# SPE_router_spe.net
KiCad netlist of a schematic drawn in Altium Designer
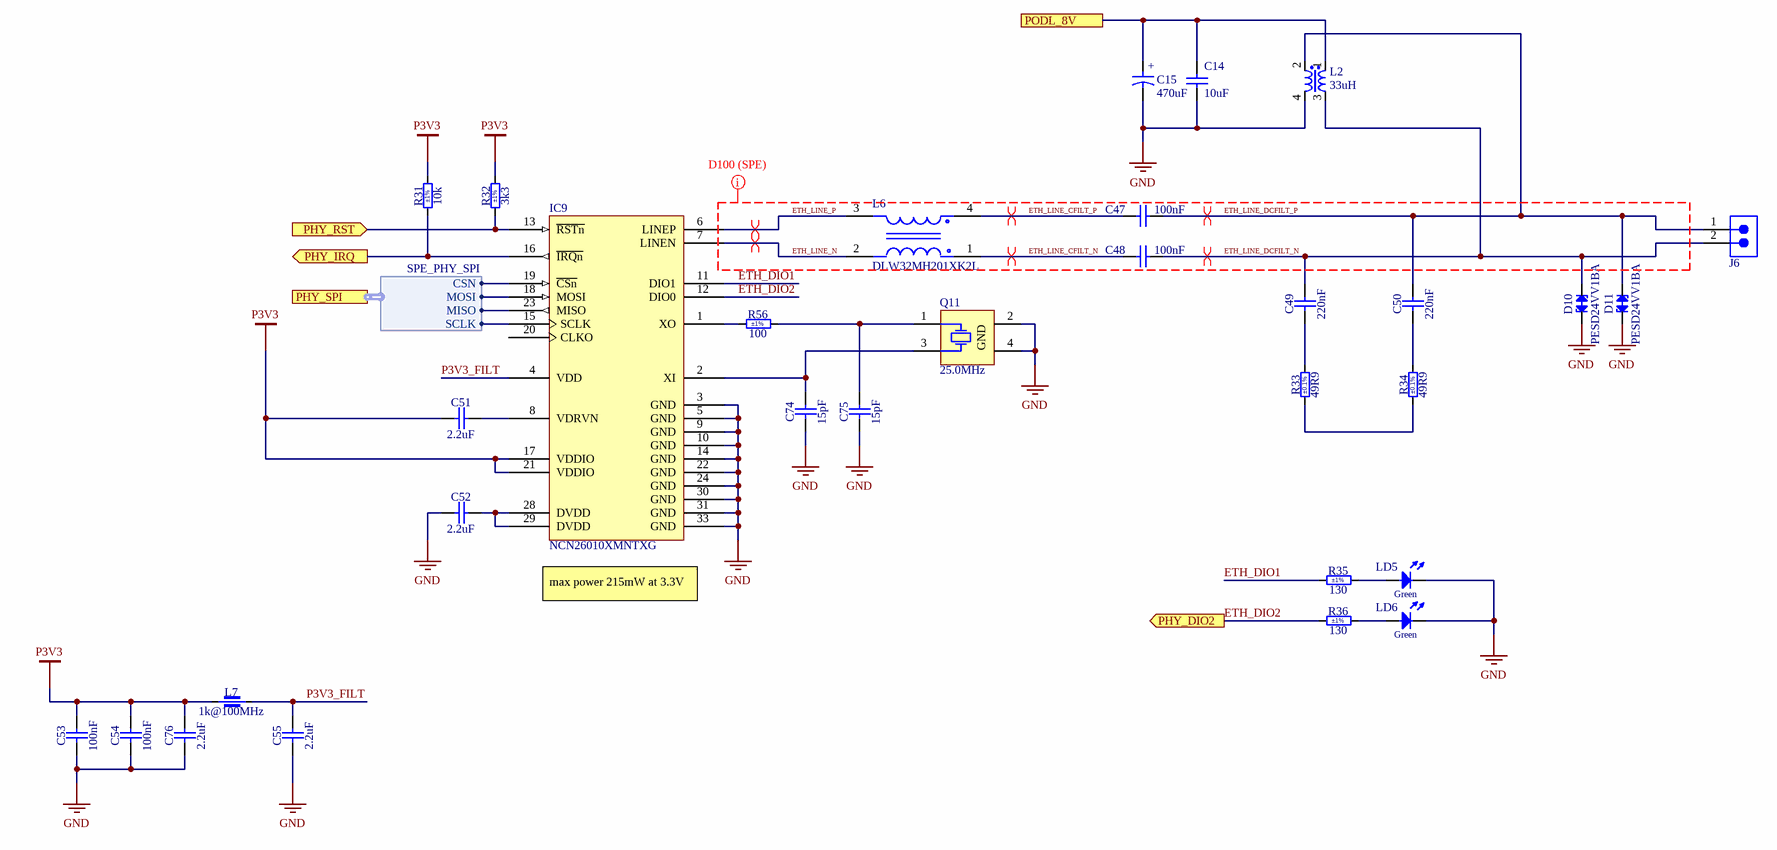
[diagram p0: SPE_router_spe.SchDoc]

(export (version "E")
  (design (tool "Eeschema 10.0.6"))
  (components
    (comp (ref "C14")
      (value "10uF")
      (footprint "CAPC3216X180N")
      (description "Non-polarised capacitor")
      (fields
        (field (name "PART NUMBER") "CC1206_10UF_25V_10%_X7R")
        (field (name "VOLTAGE") "25V")
        (field (name "AUTHOR") "CERN DEM JLC")
      )
      (libsource (lib "Capacitors") (part "Capacitor - non polarized"))
    )
    (comp (ref "C15")
      (value "470uF")
      (footprint "CAPAE830X1020N")
      (description "Polarised capacitor")
      (fields
        (field (name "PART NUMBER") "CAE830-1020_470UF_16V_20%")
        (field (name "VOLTAGE") "16V")
        (field (name "AUTHOR") "CERN DEM JLC")
      )
      (libsource (lib "Capacitors") (part "Capacitor - polarized"))
    )
    (comp (ref "C47")
      (value "100nF")
      (footprint "CAPC1005X55N")
      (description "Non-polarised capacitor")
      (fields (field (name "PART NUMBER") "CC0402_100NF_50V_10%_X7R"))
      (libsource (lib "Capacitors") (part "Capacitor - non polarized"))
    )
    (comp (ref "C48")
      (value "100nF")
      (footprint "CAPC1005X55N")
      (description "Non-polarised capacitor")
      (fields (field (name "PART NUMBER") "CC0402_100NF_50V_10%_X7R"))
      (libsource (lib "Capacitors") (part "Capacitor - non polarized"))
    )
    (comp (ref "C49")
      (value "220nF")
      (footprint "CAPC2012X135N")
      (description "Non-polarised capacitor")
      (fields
        (field (name "PART NUMBER") "CC0805_220NF_100V_10%_X7R")
        (field (name "VOLTAGE") "100V")
        (field (name "AUTHOR") "CERN DEM JLC")
      )
      (libsource (lib "Capacitors") (part "Capacitor - non polarized"))
    )
    (comp (ref "C50")
      (value "220nF")
      (footprint "CAPC2012X135N")
      (description "Non-polarised capacitor")
      (fields
        (field (name "PART NUMBER") "CC0805_220NF_100V_10%_X7R")
        (field (name "VOLTAGE") "100V")
        (field (name "AUTHOR") "CERN DEM JLC")
      )
      (libsource (lib "Capacitors") (part "Capacitor - non polarized"))
    )
    (comp (ref "C51")
      (value "2.2uF")
      (footprint "CAPC1005X55N")
      (description "Non-polarised capacitor")
      (fields (field (name "PART NUMBER") "CC0402_2.2UF_6.3V_10%_X5R"))
      (libsource (lib "Capacitors") (part "Capacitor - non polarized"))
    )
    (comp (ref "C52")
      (value "2.2uF")
      (footprint "CAPC1005X55N")
      (description "Non-polarised capacitor")
      (fields (field (name "PART NUMBER") "CC0402_2.2UF_6.3V_10%_X5R"))
      (libsource (lib "Capacitors") (part "Capacitor - non polarized"))
    )
    (comp (ref "C53")
      (value "100nF")
      (footprint "CAPC1005X55N")
      (description "Non-polarised capacitor")
      (fields
        (field (name "PART NUMBER") "CC0402_100NF_16V_10%_X7R")
        (field (name "VOLTAGE") "16V")
        (field (name "AUTHOR") "CERN DEM JLC")
      )
      (libsource (lib "Capacitors") (part "Capacitor - non polarized"))
    )
    (comp (ref "C54")
      (value "100nF")
      (footprint "CAPC1005X55N")
      (description "Non-polarised capacitor")
      (fields
        (field (name "PART NUMBER") "CC0402_100NF_16V_10%_X7R")
        (field (name "VOLTAGE") "16V")
        (field (name "AUTHOR") "CERN DEM JLC")
      )
      (libsource (lib "Capacitors") (part "Capacitor - non polarized"))
    )
    (comp (ref "C55")
      (value "2.2uF")
      (footprint "CAPC1005X55N")
      (description "Non-polarised capacitor")
      (fields (field (name "PART NUMBER") "CC0402_2.2UF_6.3V_10%_X5R"))
      (libsource (lib "Capacitors") (part "Capacitor - non polarized"))
    )
    (comp (ref "C74")
      (value "15pF")
      (footprint "CAPC1005X55N")
      (description "Non-polarised capacitor")
      (fields
        (field (name "PART NUMBER") "CC0402_15PF_50V_5%_C0G")
        (field (name "VOLTAGE") "50V")
        (field (name "AUTHOR") "CERN DEM JLC")
      )
      (libsource (lib "Capacitors") (part "Capacitor - non polarized"))
    )
    (comp (ref "C75")
      (value "15pF")
      (footprint "CAPC1005X55N")
      (description "Non-polarised capacitor")
      (fields
        (field (name "PART NUMBER") "CC0402_15PF_50V_5%_C0G")
        (field (name "VOLTAGE") "50V")
        (field (name "AUTHOR") "CERN DEM JLC")
      )
      (libsource (lib "Capacitors") (part "Capacitor - non polarized"))
    )
    (comp (ref "C76")
      (value "2.2uF")
      (footprint "CAPC1005X55N")
      (description "Non-polarised capacitor")
      (fields (field (name "PART NUMBER") "CC0402_2.2UF_6.3V_10%_X5R"))
      (libsource (lib "Capacitors") (part "Capacitor - non polarized"))
    )
    (comp (ref "D10")
      (value "PESD24VV1BA")
      (footprint "SOD2512X110N")
      (description "Bi-Directional ESD Protection Diode")
      (fields
        (field (name "VOLTAGE") "24V")
        (field (name "POWER") "200W")
        (field (name "AUTHOR") "CERN DEM JLC")
      )
      (libsource (lib "ICs And Semiconductors") (part "Diode ESD Bi-Directional"))
    )
    (comp (ref "D11")
      (value "PESD24VV1BA")
      (footprint "SOD2512X110N")
      (description "Bi-Directional ESD Protection Diode")
      (fields
        (field (name "VOLTAGE") "24V")
        (field (name "POWER") "200W")
        (field (name "AUTHOR") "CERN DEM JLC")
      )
      (libsource (lib "ICs And Semiconductors") (part "Diode ESD Bi-Directional"))
    )
    (comp (ref "IC9")
      (value "NCN26010XMNTXG")
      (footprint "QFN40P400X400X100_HS-33N")
      (description "Ethernet Controller, 10 Mb/s, Single-Pair, MAC + PHY, 802.3cg, 10BASE−T1S Compliant")
      (fields (field (name "MANUFACTURER") "ON Semiconductor"))
      (libsource (lib "DiPho_lib") (part "NCN26010XMNTXG"))
    )
    (comp (ref "J6")
      (value "691382040002")
      (footprint "691382040002")
      (description "WR-TBL Series 382 Horizontal PCB Header with Flanges, THT, pitch 2.5mm, 2p")
      (fields (field (name "MANUFACTURER") "Wurth Elektronik"))
      (libsource (lib "SPE_router_lib") (part "691382040002"))
    )
    (comp (ref "L2")
      (value "33uH")
      (footprint "MSD1278H-333MED")
      (description "coupled inductor, ferrite core, SMT, RoHS")
      (fields
        (field (name "MANUFACTURER") "Coilcraft")
        (field (name "MANUFACTURER PART NUMBER") "MSD1278H-333MED")
      )
      (libsource (lib "SPE_router_lib") (part "MSD1278H-333MED"))
    )
    (comp (ref "L6")
      (value "DLW32MH201XK2L")
      (footprint "FP-DLW32MH201XK2L-MFG")
      (description "200UH-20%/+50% (AT 0.1MHZ)70MA R")
      (fields
        (field (name "OCTOPART") "https://octopart.com/dlw32mh201xk2l-murata-91401020")
        (field (name "MANUFACTURER") "Murata")
      )
      (libsource (lib "Altium Content Vault") (part "fd31f9bded309692d3ecdb47de416e9"))
    )
    (comp (ref "L7")
      (value "1k@100MHz")
      (footprint "INDC1608X100N")
      (fields
        (field (name "PART NUMBER") "IND0603_WURTH_74279266")
        (field (name "POWER") "200mA")
        (field (name "TOLERANCE") "±25%")
        (field (name "AUTHOR") "CERN DEM JLC")
      )
      (libsource (lib "Inductors & Transformers") (part "Ferrite Bead"))
    )
    (comp (ref "LD5")
      (value "Green")
      (footprint "LED_AVAGO_HSME-C110")
      (description "LED Green 1C 2A")
      (fields
        (field (name "PART NUMBER") "LED_AVAGO_HSME-C110")
        (field (name "MANUFACTURER") "AVAGO TECHNOLOGIES")
        (field (name "AUTHOR") "CERN DEM JMW")
      )
      (libsource (lib "ICs And Semiconductors") (part "LED Green 1C 2A"))
    )
    (comp (ref "LD6")
      (value "Green")
      (footprint "LED_AVAGO_HSME-C110")
      (description "LED Green 1C 2A")
      (fields
        (field (name "PART NUMBER") "LED_AVAGO_HSME-C110")
        (field (name "MANUFACTURER") "AVAGO TECHNOLOGIES")
        (field (name "AUTHOR") "CERN DEM JMW")
      )
      (libsource (lib "ICs And Semiconductors") (part "LED Green 1C 2A"))
    )
    (comp (ref "Q11")
      (value "25.0MHz")
      (footprint "XTAL_KYOCERA_CX3225SB")
      (description "Crystal 25 Mhz 12PF SMD")
      (fields
        (field (name "MANUFACTURER") "ECS International")
        (field (name "MANUFACTURER PART NUMBER") "ECS-250-12-33B-CWY-TR3")
      )
      (libsource (lib "SPE_router_lib") (part "ECS-250-12-33B-CWY-TR3"))
    )
    (comp (ref "R31")
      (value "10k")
      (footprint "RESC1005X40N")
      (description "Resistor - 1%")
      (fields
        (field (name "TOLERANCE") "±1%")
        (field (name "PART NUMBER") "R0402_10K_1%_0.0625W_100PPM")
        (field (name "POWER") "0.0625W")
        (field (name "AUTHOR") "CERN DEM JLC")
      )
      (libsource (lib "Resistors") (part "Resistor - 1%"))
    )
    (comp (ref "R32")
      (value "3k3")
      (footprint "RESC1005X40N")
      (description "Resistor - 1%")
      (fields
        (field (name "TOLERANCE") "±1%")
        (field (name "PART NUMBER") "R0402_3K3_1%_0.0625W_100PPM")
        (field (name "POWER") "0.0625W")
        (field (name "AUTHOR") "CERN DEM JLC")
      )
      (libsource (lib "Resistors") (part "Resistor - 1%"))
    )
    (comp (ref "R33")
      (value "49R9")
      (footprint "RESC1608X55N")
      (description "Resistor - 0.1%")
      (fields
        (field (name "TOLERANCE") "±0.1%")
        (field (name "PART NUMBER") "R0603_49R9_0.1%_0.063W_10PPM")
        (field (name "POWER") "0.063W")
        (field (name "AUTHOR") "CERN DEM JLC")
      )
      (libsource (lib "Resistors") (part "Resistor - 0.1%"))
    )
    (comp (ref "R34")
      (value "49R9")
      (footprint "RESC1608X55N")
      (description "Resistor - 0.1%")
      (fields
        (field (name "TOLERANCE") "±0.1%")
        (field (name "PART NUMBER") "R0603_49R9_0.1%_0.063W_10PPM")
        (field (name "POWER") "0.063W")
        (field (name "AUTHOR") "CERN DEM JLC")
      )
      (libsource (lib "Resistors") (part "Resistor - 0.1%"))
    )
    (comp (ref "R35")
      (value "130")
      (footprint "RESC1005X40N")
      (description "Resistor - 1%")
      (fields
        (field (name "TOLERANCE") "±1%")
        (field (name "PART NUMBER") "R0402_130R_1%_0.0625W_100PPM")
        (field (name "POWER") "0.0625W")
        (field (name "AUTHOR") "CERN DEM JLC")
      )
      (libsource (lib "Resistors") (part "Resistor - 1%"))
    )
    (comp (ref "R36")
      (value "130")
      (footprint "RESC1005X40N")
      (description "Resistor - 1%")
      (fields
        (field (name "TOLERANCE") "±1%")
        (field (name "PART NUMBER") "R0402_130R_1%_0.0625W_100PPM")
        (field (name "POWER") "0.0625W")
        (field (name "AUTHOR") "CERN DEM JLC")
      )
      (libsource (lib "Resistors") (part "Resistor - 1%"))
    )
    (comp (ref "R56")
      (value "100")
      (footprint "RESC1005X40N")
      (description "Resistor - 1%")
      (fields
        (field (name "PART NUMBER") "R0402_100R_1%_0.0625W_100PPM")
        (field (name "MANUFACTURER") "GENERIC")
        (field (name "TOLERANCE") "±1%")
        (field (name "AUTHOR") "CERN DEM JLC")
      )
      (libsource (lib "Resistors") (part "Resistor - 1%"))
    )
  )
  (nets
    (net (code "2") (name "/CSN") (class "Default")
      (node (ref "IC9") (pin "19") (pinfunction "~{CSn}_19") (pintype "input"))
    )
    (net (code "3") (name "/ETH_DIO1") (class "Default")
      (node (ref "IC9") (pin "11") (pinfunction "DIO1_11") (pintype "passive"))
      (node (ref "R35") (pin "1") (pinfunction "1_1") (pintype "passive"))
    )
    (net (code "4") (name "/ETH_DIO2") (class "Default")
      (node (ref "IC9") (pin "12") (pinfunction "DIO0_12") (pintype "passive"))
      (node (ref "R36") (pin "1") (pinfunction "1_1") (pintype "passive"))
    )
    (net (code "5") (name "/ETH_LINE_CFILT_N") (class "Default")
      (node (ref "C48") (pin "1") (pinfunction "1_1") (pintype "passive"))
      (node (ref "L6") (pin "1") (pinfunction "1_1") (pintype "passive"))
    )
    (net (code "6") (name "/ETH_LINE_CFILT_P") (class "Default")
      (node (ref "C47") (pin "1") (pinfunction "1_1") (pintype "passive"))
      (node (ref "L6") (pin "4") (pinfunction "4_4") (pintype "passive"))
    )
    (net (code "7") (name "/ETH_LINE_DCFILT_N") (class "Default")
      (node (ref "C48") (pin "2") (pinfunction "2_2") (pintype "passive"))
      (node (ref "C49") (pin "2") (pinfunction "2_2") (pintype "passive"))
      (node (ref "D10") (pin "2") (pinfunction "C_2") (pintype "passive"))
      (node (ref "J6") (pin "2") (pinfunction "2_2") (pintype "passive"))
      (node (ref "L2") (pin "3") (pinfunction "3_3") (pintype "passive"))
    )
    (net (code "8") (name "/ETH_LINE_DCFILT_P") (class "Default")
      (node (ref "C47") (pin "2") (pinfunction "2_2") (pintype "passive"))
      (node (ref "C50") (pin "2") (pinfunction "2_2") (pintype "passive"))
      (node (ref "D11") (pin "2") (pinfunction "C_2") (pintype "passive"))
      (node (ref "J6") (pin "1") (pinfunction "1_1") (pintype "passive"))
      (node (ref "L2") (pin "2") (pinfunction "2_2") (pintype "passive"))
    )
    (net (code "9") (name "/ETH_LINE_N") (class "Default")
      (node (ref "IC9") (pin "7") (pinfunction "LINEN_7") (pintype "passive"))
      (node (ref "L6") (pin "2") (pinfunction "2_2") (pintype "passive"))
    )
    (net (code "10") (name "/ETH_LINE_P") (class "Default")
      (node (ref "IC9") (pin "6") (pinfunction "LINEP_6") (pintype "passive"))
      (node (ref "L6") (pin "3") (pinfunction "3_3") (pintype "passive"))
    )
    (net (code "11") (name "/MISO") (class "Default")
      (node (ref "IC9") (pin "23") (pinfunction "MISO_23") (pintype "output"))
    )
    (net (code "12") (name "/MOSI") (class "Default")
      (node (ref "IC9") (pin "18") (pinfunction "MOSI_18") (pintype "input"))
    )
    (net (code "13") (name "/P3V3_FILT") (class "Default")
      (node (ref "C55") (pin "2") (pinfunction "2_2") (pintype "passive"))
      (node (ref "IC9") (pin "4") (pinfunction "VDD_4") (pintype "power_in"))
      (node (ref "L7") (pin "2") (pinfunction "2_2") (pintype "passive"))
    )
    (net (code "14") (name "/PHY_IRQ") (class "Default")
      (node (ref "IC9") (pin "16") (pinfunction "~{IRQn}_16") (pintype "output"))
      (node (ref "R31") (pin "1") (pinfunction "1_1") (pintype "passive"))
    )
    (net (code "15") (name "/PHY_RST") (class "Default")
      (node (ref "IC9") (pin "13") (pinfunction "~{RSTn}_13") (pintype "input"))
      (node (ref "R32") (pin "1") (pinfunction "1_1") (pintype "passive"))
    )
    (net (code "16") (name "/PODL_8V") (class "Default")
      (node (ref "C14") (pin "2") (pinfunction "2_2") (pintype "passive"))
      (node (ref "C15") (pin "1") (pinfunction "1_1") (pintype "passive"))
      (node (ref "L2") (pin "1") (pinfunction "1_1") (pintype "passive"))
    )
    (net (code "17") (name "/SCLK") (class "Default")
      (node (ref "IC9") (pin "15") (pinfunction "SCLK_15") (pintype "passive"))
    )
    (net (code "19") (name "GND") (class "Default")
      (node (ref "C14") (pin "1") (pinfunction "1_1") (pintype "passive"))
      (node (ref "C15") (pin "2") (pinfunction "2_2") (pintype "passive"))
      (node (ref "C52") (pin "1") (pinfunction "1_1") (pintype "passive"))
      (node (ref "C53") (pin "1") (pinfunction "1_1") (pintype "passive"))
      (node (ref "C54") (pin "1") (pinfunction "1_1") (pintype "passive"))
      (node (ref "C55") (pin "1") (pinfunction "1_1") (pintype "passive"))
      (node (ref "C74") (pin "1") (pinfunction "1_1") (pintype "passive"))
      (node (ref "C75") (pin "1") (pinfunction "1_1") (pintype "passive"))
      (node (ref "C76") (pin "1") (pinfunction "1_1") (pintype "passive"))
      (node (ref "D10") (pin "1") (pinfunction "C_1") (pintype "passive"))
      (node (ref "D11") (pin "1") (pinfunction "C_1") (pintype "passive"))
      (node (ref "IC9") (pin "10") (pinfunction "GND_10") (pintype "power_in"))
      (node (ref "IC9") (pin "14") (pinfunction "GND_14") (pintype "power_in"))
      (node (ref "IC9") (pin "22") (pinfunction "GND_22") (pintype "power_in"))
      (node (ref "IC9") (pin "24") (pinfunction "GND_24") (pintype "power_in"))
      (node (ref "IC9") (pin "3") (pinfunction "GND_3") (pintype "power_in"))
      (node (ref "IC9") (pin "30") (pinfunction "GND_30") (pintype "power_in"))
      (node (ref "IC9") (pin "31") (pinfunction "GND_31") (pintype "power_in"))
      (node (ref "IC9") (pin "33") (pinfunction "GND_33") (pintype "power_in"))
      (node (ref "IC9") (pin "5") (pinfunction "GND_5") (pintype "power_in"))
      (node (ref "IC9") (pin "9") (pinfunction "GND_9") (pintype "power_in"))
      (node (ref "L2") (pin "4") (pinfunction "4_4") (pintype "passive"))
      (node (ref "LD5") (pin "1") (pinfunction "C_1") (pintype "passive"))
      (node (ref "LD6") (pin "1") (pinfunction "C_1") (pintype "passive"))
      (node (ref "Q11") (pin "2") (pinfunction "GND_2") (pintype "power_in"))
      (node (ref "Q11") (pin "4") (pinfunction "GND_4") (pintype "power_in"))
    )
    (net (code "20") (name "Net-(C49-Pad1)") (class "Default")
      (node (ref "C49") (pin "1") (pinfunction "1_1") (pintype "passive"))
      (node (ref "R33") (pin "2") (pinfunction "2_2") (pintype "passive"))
    )
    (net (code "21") (name "Net-(C50-Pad1)") (class "Default")
      (node (ref "C50") (pin "1") (pinfunction "1_1") (pintype "passive"))
      (node (ref "R34") (pin "2") (pinfunction "2_2") (pintype "passive"))
    )
    (net (code "22") (name "Net-(C52-Pad2)") (class "Default")
      (node (ref "C52") (pin "2") (pinfunction "2_2") (pintype "passive"))
      (node (ref "IC9") (pin "28") (pinfunction "DVDD_28") (pintype "power_in"))
      (node (ref "IC9") (pin "29") (pinfunction "DVDD_29") (pintype "power_in"))
    )
    (net (code "23") (name "Net-(C75-Pad2)") (class "Default")
      (node (ref "C75") (pin "2") (pinfunction "2_2") (pintype "passive"))
      (node (ref "Q11") (pin "1") (pinfunction "X_1") (pintype "passive"))
      (node (ref "R56") (pin "2") (pinfunction "2_2") (pintype "passive"))
    )
    (net (code "24") (name "Net-(IC9-VDRVN)") (class "Default")
      (node (ref "C51") (pin "2") (pinfunction "2_2") (pintype "passive"))
      (node (ref "IC9") (pin "8") (pinfunction "VDRVN_8") (pintype "power_in"))
    )
    (net (code "25") (name "Net-(IC9-XI)") (class "Default")
      (node (ref "C74") (pin "2") (pinfunction "2_2") (pintype "passive"))
      (node (ref "IC9") (pin "2") (pinfunction "XI_2") (pintype "passive"))
      (node (ref "Q11") (pin "3") (pinfunction "X_3") (pintype "passive"))
    )
    (net (code "26") (name "Net-(IC9-XO)") (class "Default")
      (node (ref "IC9") (pin "1") (pinfunction "XO_1") (pintype "passive"))
      (node (ref "R56") (pin "1") (pinfunction "1_1") (pintype "passive"))
    )
    (net (code "27") (name "Net-(LD5-A)") (class "Default")
      (node (ref "LD5") (pin "2") (pinfunction "A_2") (pintype "passive"))
      (node (ref "R35") (pin "2") (pinfunction "2_2") (pintype "passive"))
    )
    (net (code "28") (name "Net-(LD6-A)") (class "Default")
      (node (ref "LD6") (pin "2") (pinfunction "A_2") (pintype "passive"))
      (node (ref "R36") (pin "2") (pinfunction "2_2") (pintype "passive"))
    )
    (net (code "29") (name "Net-(R33-Pad1)") (class "Default")
      (node (ref "R33") (pin "1") (pinfunction "1_1") (pintype "passive"))
      (node (ref "R34") (pin "1") (pinfunction "1_1") (pintype "passive"))
    )
    (net (code "30") (name "P3V3") (class "Default")
      (node (ref "C51") (pin "1") (pinfunction "1_1") (pintype "passive"))
      (node (ref "C53") (pin "2") (pinfunction "2_2") (pintype "passive"))
      (node (ref "C54") (pin "2") (pinfunction "2_2") (pintype "passive"))
      (node (ref "C76") (pin "2") (pinfunction "2_2") (pintype "passive"))
      (node (ref "IC9") (pin "17") (pinfunction "VDDIO_17") (pintype "power_in"))
      (node (ref "IC9") (pin "21") (pinfunction "VDDIO_21") (pintype "power_in"))
      (node (ref "L7") (pin "1") (pinfunction "1_1") (pintype "passive"))
      (node (ref "R31") (pin "2") (pinfunction "2_2") (pintype "passive"))
      (node (ref "R32") (pin "2") (pinfunction "2_2") (pintype "passive"))
    )
    (net (code "31") (name "unconnected-(IC9-CLKO-Pad20)") (class "Default")
      (node (ref "IC9") (pin "20") (pinfunction "CLKO_20") (pintype "passive"))
    )
  )
)
